# ALU.net
KiCad netlist of a schematic drawn in Altium Designer
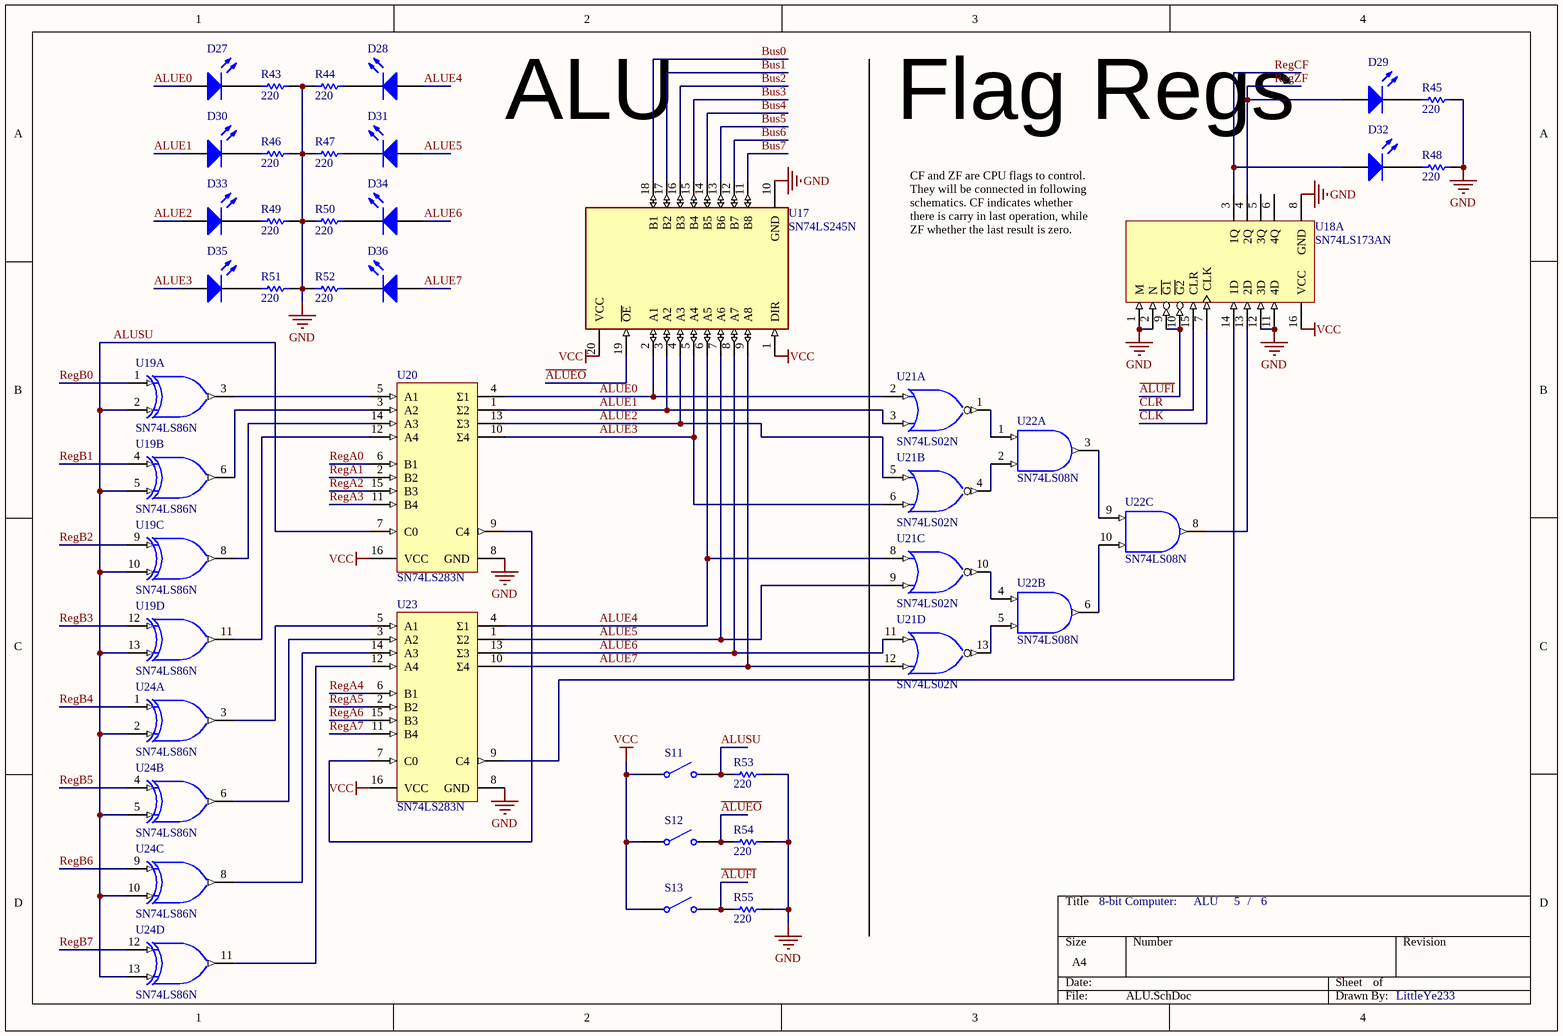
[diagram p0: ALU.SchDoc]

(export (version "E")
  (design (tool "Eeschema 10.0.6"))
  (components
    (comp (ref "D27")
      (value "Light-Emitting Diode")
      (libsource (lib "Simulation Generic Components") (part "LED"))
    )
    (comp (ref "D28")
      (value "Light-Emitting Diode")
      (libsource (lib "Simulation Generic Components") (part "LED"))
    )
    (comp (ref "D29")
      (value "Light-Emitting Diode")
      (libsource (lib "Simulation Generic Components") (part "LED"))
    )
    (comp (ref "D30")
      (value "Light-Emitting Diode")
      (libsource (lib "Simulation Generic Components") (part "LED"))
    )
    (comp (ref "D31")
      (value "Light-Emitting Diode")
      (libsource (lib "Simulation Generic Components") (part "LED"))
    )
    (comp (ref "D32")
      (value "Light-Emitting Diode")
      (libsource (lib "Simulation Generic Components") (part "LED"))
    )
    (comp (ref "D33")
      (value "Light-Emitting Diode")
      (libsource (lib "Simulation Generic Components") (part "LED"))
    )
    (comp (ref "D34")
      (value "Light-Emitting Diode")
      (libsource (lib "Simulation Generic Components") (part "LED"))
    )
    (comp (ref "D35")
      (value "Light-Emitting Diode")
      (libsource (lib "Simulation Generic Components") (part "LED"))
    )
    (comp (ref "D36")
      (value "Light-Emitting Diode")
      (libsource (lib "Simulation Generic Components") (part "LED"))
    )
    (comp (ref "R43")
      (value "220")
      (description "Resistor")
      (libsource (lib "Simulation Generic Components") (part "Resistor"))
    )
    (comp (ref "R44")
      (value "220")
      (description "Resistor")
      (libsource (lib "Simulation Generic Components") (part "Resistor"))
    )
    (comp (ref "R45")
      (value "220")
      (description "Resistor")
      (libsource (lib "Simulation Generic Components") (part "Resistor"))
    )
    (comp (ref "R46")
      (value "220")
      (description "Resistor")
      (libsource (lib "Simulation Generic Components") (part "Resistor"))
    )
    (comp (ref "R47")
      (value "220")
      (description "Resistor")
      (libsource (lib "Simulation Generic Components") (part "Resistor"))
    )
    (comp (ref "R48")
      (value "220")
      (description "Resistor")
      (libsource (lib "Simulation Generic Components") (part "Resistor"))
    )
    (comp (ref "R49")
      (value "220")
      (description "Resistor")
      (libsource (lib "Simulation Generic Components") (part "Resistor"))
    )
    (comp (ref "R50")
      (value "220")
      (description "Resistor")
      (libsource (lib "Simulation Generic Components") (part "Resistor"))
    )
    (comp (ref "R51")
      (value "220")
      (description "Resistor")
      (libsource (lib "Simulation Generic Components") (part "Resistor"))
    )
    (comp (ref "R52")
      (value "220")
      (description "Resistor")
      (libsource (lib "Simulation Generic Components") (part "Resistor"))
    )
    (comp (ref "R53")
      (value "220")
      (description "Resistor")
      (libsource (lib "Simulation Generic Components") (part "Resistor"))
    )
    (comp (ref "R54")
      (value "220")
      (description "Resistor")
      (libsource (lib "Simulation Generic Components") (part "Resistor"))
    )
    (comp (ref "R55")
      (value "220")
      (description "Resistor")
      (libsource (lib "Simulation Generic Components") (part "Resistor"))
    )
    (comp (ref "S11")
      (value "Single-Pole, Single-Throw Switch")
      (libsource (lib "Simulation Generic Components") (part "SPST SW"))
    )
    (comp (ref "S12")
      (value "Single-Pole, Single-Throw Switch")
      (libsource (lib "Simulation Generic Components") (part "SPST SW"))
    )
    (comp (ref "S13")
      (value "Single-Pole, Single-Throw Switch")
      (libsource (lib "Simulation Generic Components") (part "SPST SW"))
    )
    (comp (ref "U17")
      (value "SN74LS245N")
      (footprint "FP-N0020A-MFG")
      (description "IC TXRX NON-INVERT 5.25V 20DIP")
      (libsource (lib "SN74LS245N") (part "CMP-1620-00419-3"))
    )
    (comp (ref "U18")
      (value "SN74LS173AN")
      (footprint "N0016A")
      (description "4-Bit D-type Registers with 3-State Outputs, N0016A, TUBE")
      (fields
        (field (name "MANUFACTURER") "Texas Instruments")
        (field (name "GENERIC PART NUMBER") "SN74LS173A")
      )
      (libsource (lib "SN74LS173AN") (part "CMP-1619-00777-2"))
    )
    (comp (ref "U19") (value "SN74LS86N") (libsource (lib "SN74LS86N") (part "SN74LS86N")))
    (comp (ref "U20")
      (value "SN74LS283N")
      (footprint "N0016A")
      (description "4-Bit Binary Full Adders With Fast Carry, N0016A, TUBE")
      (fields
        (field (name "GENERIC PART NUMBER") "SN74LS283")
        (field (name "MANUFACTURER") "Texas Instruments")
      )
      (libsource (lib "SN74LS283N") (part "CMP-1623-00518-2"))
    )
    (comp (ref "U21")
      (value "SN74LS02N")
      (footprint "N0014A")
      (description "Quad 2-input positive-NOR gates, N0014A, TUBE")
      (fields
        (field (name "GENERIC PART NUMBER") "SN74LS02")
        (field (name "MANUFACTURER") "Texas Instruments")
      )
      (libsource (lib "SN74LS02N") (part "CMP-0806-00181-3"))
    )
    (comp (ref "U22")
      (value "SN74LS08N")
      (footprint "N0014A")
      (description "Quadruple 2-Input Positive-AND Gates, N0014A, TUBE")
      (fields
        (field (name "MANUFACTURER") "Texas Instruments")
        (field (name "GENERIC PART NUMBER") "SN74LS08")
      )
      (libsource (lib "SN74LS08N") (part "CMP-0777-00259-3"))
    )
    (comp (ref "U23")
      (value "SN74LS283N")
      (footprint "N0016A")
      (description "4-Bit Binary Full Adders With Fast Carry, N0016A, TUBE")
      (fields
        (field (name "GENERIC PART NUMBER") "SN74LS283")
        (field (name "MANUFACTURER") "Texas Instruments")
      )
      (libsource (lib "SN74LS283N") (part "CMP-1623-00518-2"))
    )
    (comp (ref "U24") (value "SN74LS86N") (libsource (lib "SN74LS86N") (part "SN74LS86N")))
  )
  (nets
    (net (code "1") (name "/ALUE0") (class "Default")
      (node (ref "D27") (pin "1") (pinfunction "A_1") (pintype "passive"))
      (node (ref "U17") (pin "2") (pinfunction "A1_2") (pintype "bidirectional"))
      (node (ref "U20") (pin "4") (pinfunction "Σ1_4") (pintype "passive"))
      (node (ref "U21") (pin "2") (pinfunction "1A_2") (pintype "input"))
    )
    (net (code "2") (name "/ALUE1") (class "Default")
      (node (ref "D30") (pin "1") (pinfunction "A_1") (pintype "passive"))
      (node (ref "U17") (pin "3") (pinfunction "A2_3") (pintype "bidirectional"))
      (node (ref "U20") (pin "1") (pinfunction "Σ2_1") (pintype "passive"))
      (node (ref "U21") (pin "3") (pinfunction "1B_3") (pintype "input"))
    )
    (net (code "3") (name "/ALUE2") (class "Default")
      (node (ref "D33") (pin "1") (pinfunction "A_1") (pintype "passive"))
      (node (ref "U17") (pin "4") (pinfunction "A3_4") (pintype "bidirectional"))
      (node (ref "U20") (pin "13") (pinfunction "Σ3_13") (pintype "passive"))
      (node (ref "U21") (pin "5") (pinfunction "2A_5") (pintype "input"))
    )
    (net (code "4") (name "/ALUE3") (class "Default")
      (node (ref "D35") (pin "1") (pinfunction "A_1") (pintype "passive"))
      (node (ref "U17") (pin "5") (pinfunction "A4_5") (pintype "bidirectional"))
      (node (ref "U20") (pin "10") (pinfunction "Σ4_10") (pintype "passive"))
      (node (ref "U21") (pin "6") (pinfunction "2B_6") (pintype "input"))
    )
    (net (code "5") (name "/ALUE4") (class "Default")
      (node (ref "D28") (pin "1") (pinfunction "A_1") (pintype "passive"))
      (node (ref "U17") (pin "6") (pinfunction "A5_6") (pintype "bidirectional"))
      (node (ref "U21") (pin "8") (pinfunction "3A_8") (pintype "input"))
      (node (ref "U23") (pin "4") (pinfunction "Σ1_4") (pintype "passive"))
    )
    (net (code "6") (name "/ALUE5") (class "Default")
      (node (ref "D31") (pin "1") (pinfunction "A_1") (pintype "passive"))
      (node (ref "U17") (pin "7") (pinfunction "A6_7") (pintype "bidirectional"))
      (node (ref "U21") (pin "9") (pinfunction "3B_9") (pintype "input"))
      (node (ref "U23") (pin "1") (pinfunction "Σ2_1") (pintype "passive"))
    )
    (net (code "7") (name "/ALUE6") (class "Default")
      (node (ref "D34") (pin "1") (pinfunction "A_1") (pintype "passive"))
      (node (ref "U17") (pin "8") (pinfunction "A7_8") (pintype "bidirectional"))
      (node (ref "U21") (pin "11") (pinfunction "4A_11") (pintype "input"))
      (node (ref "U23") (pin "13") (pinfunction "Σ3_13") (pintype "passive"))
    )
    (net (code "8") (name "/ALUE7") (class "Default")
      (node (ref "D36") (pin "1") (pinfunction "A_1") (pintype "passive"))
      (node (ref "U17") (pin "9") (pinfunction "A8_9") (pintype "bidirectional"))
      (node (ref "U21") (pin "12") (pinfunction "4B_12") (pintype "input"))
      (node (ref "U23") (pin "10") (pinfunction "Σ4_10") (pintype "passive"))
    )
    (net (code "9") (name "/ALUSU") (class "Default")
      (node (ref "R53") (pin "2") (pinfunction "2_2") (pintype "passive"))
      (node (ref "S11") (pin "2") (pinfunction "2_2") (pintype "passive"))
      (node (ref "U19") (pin "10") (pinfunction "3B_10") (pintype "input"))
      (node (ref "U19") (pin "13") (pinfunction "4B_13") (pintype "input"))
      (node (ref "U19") (pin "2") (pinfunction "1B_2") (pintype "input"))
      (node (ref "U19") (pin "5") (pinfunction "2B_5") (pintype "input"))
      (node (ref "U20") (pin "7") (pinfunction "C0_7") (pintype "input"))
      (node (ref "U24") (pin "10") (pinfunction "3B_10") (pintype "input"))
      (node (ref "U24") (pin "13") (pinfunction "4B_13") (pintype "input"))
      (node (ref "U24") (pin "2") (pinfunction "1B_2") (pintype "input"))
      (node (ref "U24") (pin "5") (pinfunction "2B_5") (pintype "input"))
    )
    (net (code "10") (name "/Bus0") (class "Default")
      (node (ref "U17") (pin "18") (pinfunction "B1_18") (pintype "bidirectional"))
    )
    (net (code "11") (name "/Bus1") (class "Default")
      (node (ref "U17") (pin "17") (pinfunction "B2_17") (pintype "bidirectional"))
    )
    (net (code "12") (name "/Bus2") (class "Default")
      (node (ref "U17") (pin "16") (pinfunction "B3_16") (pintype "bidirectional"))
    )
    (net (code "13") (name "/Bus3") (class "Default")
      (node (ref "U17") (pin "15") (pinfunction "B4_15") (pintype "bidirectional"))
    )
    (net (code "14") (name "/Bus4") (class "Default")
      (node (ref "U17") (pin "14") (pinfunction "B5_14") (pintype "bidirectional"))
    )
    (net (code "15") (name "/Bus5") (class "Default")
      (node (ref "U17") (pin "13") (pinfunction "B6_13") (pintype "bidirectional"))
    )
    (net (code "16") (name "/Bus6") (class "Default")
      (node (ref "U17") (pin "12") (pinfunction "B7_12") (pintype "bidirectional"))
    )
    (net (code "17") (name "/Bus7") (class "Default")
      (node (ref "U17") (pin "11") (pinfunction "B8_11") (pintype "bidirectional"))
    )
    (net (code "18") (name "/CLK") (class "Default")
      (node (ref "U18") (pin "7") (pinfunction "CLK_7") (pintype "input"))
    )
    (net (code "19") (name "/CLR") (class "Default")
      (node (ref "U18") (pin "15") (pinfunction "CLR_15") (pintype "input"))
    )
    (net (code "20") (name "/RegA0") (class "Default")
      (node (ref "U20") (pin "6") (pinfunction "B1_6") (pintype "input"))
    )
    (net (code "21") (name "/RegA1") (class "Default")
      (node (ref "U20") (pin "2") (pinfunction "B2_2") (pintype "input"))
    )
    (net (code "22") (name "/RegA2") (class "Default")
      (node (ref "U20") (pin "15") (pinfunction "B3_15") (pintype "input"))
    )
    (net (code "23") (name "/RegA3") (class "Default")
      (node (ref "U20") (pin "11") (pinfunction "B4_11") (pintype "input"))
    )
    (net (code "24") (name "/RegA4") (class "Default")
      (node (ref "U23") (pin "6") (pinfunction "B1_6") (pintype "input"))
    )
    (net (code "25") (name "/RegA5") (class "Default")
      (node (ref "U23") (pin "2") (pinfunction "B2_2") (pintype "input"))
    )
    (net (code "26") (name "/RegA6") (class "Default")
      (node (ref "U23") (pin "15") (pinfunction "B3_15") (pintype "input"))
    )
    (net (code "27") (name "/RegA7") (class "Default")
      (node (ref "U23") (pin "11") (pinfunction "B4_11") (pintype "input"))
    )
    (net (code "28") (name "/RegB0") (class "Default")
      (node (ref "U19") (pin "1") (pinfunction "1A_1") (pintype "input"))
    )
    (net (code "29") (name "/RegB1") (class "Default")
      (node (ref "U19") (pin "4") (pinfunction "2A_4") (pintype "input"))
    )
    (net (code "30") (name "/RegB2") (class "Default")
      (node (ref "U19") (pin "9") (pinfunction "3A_9") (pintype "input"))
    )
    (net (code "31") (name "/RegB3") (class "Default")
      (node (ref "U19") (pin "12") (pinfunction "4A_12") (pintype "input"))
    )
    (net (code "32") (name "/RegB4") (class "Default")
      (node (ref "U24") (pin "1") (pinfunction "1A_1") (pintype "input"))
    )
    (net (code "33") (name "/RegB5") (class "Default")
      (node (ref "U24") (pin "4") (pinfunction "2A_4") (pintype "input"))
    )
    (net (code "34") (name "/RegB6") (class "Default")
      (node (ref "U24") (pin "9") (pinfunction "3A_9") (pintype "input"))
    )
    (net (code "35") (name "/RegB7") (class "Default")
      (node (ref "U24") (pin "12") (pinfunction "4A_12") (pintype "input"))
    )
    (net (code "36") (name "/RegCF") (class "Default")
      (node (ref "D32") (pin "1") (pinfunction "A_1") (pintype "passive"))
      (node (ref "U18") (pin "3") (pinfunction "1Q_3") (pintype "tri_state"))
    )
    (net (code "37") (name "/RegZF") (class "Default")
      (node (ref "D29") (pin "1") (pinfunction "A_1") (pintype "passive"))
      (node (ref "U18") (pin "4") (pinfunction "2Q_4") (pintype "tri_state"))
    )
    (net (code "38") (name "/~{ALUEO}") (class "Default")
      (node (ref "R54") (pin "2") (pinfunction "2_2") (pintype "passive"))
      (node (ref "S12") (pin "2") (pinfunction "2_2") (pintype "passive"))
      (node (ref "U17") (pin "19") (pinfunction "~{OE}_19") (pintype "input"))
    )
    (net (code "39") (name "/~{ALUFI}") (class "Default")
      (node (ref "R55") (pin "2") (pinfunction "2_2") (pintype "passive"))
      (node (ref "S13") (pin "2") (pinfunction "2_2") (pintype "passive"))
      (node (ref "U18") (pin "10") (pinfunction "~{G2}_10") (pintype "input"))
      (node (ref "U18") (pin "9") (pinfunction "~{G1}_9") (pintype "input"))
    )
    (net (code "40") (name "GND") (class "Default")
      (node (ref "R43") (pin "2") (pinfunction "2_2") (pintype "passive"))
      (node (ref "R44") (pin "1") (pinfunction "1_1") (pintype "passive"))
      (node (ref "R45") (pin "2") (pinfunction "2_2") (pintype "passive"))
      (node (ref "R46") (pin "2") (pinfunction "2_2") (pintype "passive"))
      (node (ref "R47") (pin "1") (pinfunction "1_1") (pintype "passive"))
      (node (ref "R48") (pin "2") (pinfunction "2_2") (pintype "passive"))
      (node (ref "R49") (pin "2") (pinfunction "2_2") (pintype "passive"))
      (node (ref "R50") (pin "1") (pinfunction "1_1") (pintype "passive"))
      (node (ref "R51") (pin "2") (pinfunction "2_2") (pintype "passive"))
      (node (ref "R52") (pin "1") (pinfunction "1_1") (pintype "passive"))
      (node (ref "R53") (pin "1") (pinfunction "1_1") (pintype "passive"))
      (node (ref "R54") (pin "1") (pinfunction "1_1") (pintype "passive"))
      (node (ref "R55") (pin "1") (pinfunction "1_1") (pintype "passive"))
      (node (ref "U17") (pin "10") (pinfunction "GND_10") (pintype "power_in"))
      (node (ref "U18") (pin "1") (pinfunction "M_1") (pintype "input"))
      (node (ref "U18") (pin "11") (pinfunction "4D_11") (pintype "input"))
      (node (ref "U18") (pin "12") (pinfunction "3D_12") (pintype "input"))
      (node (ref "U18") (pin "2") (pinfunction "N_2") (pintype "input"))
      (node (ref "U18") (pin "8") (pinfunction "GND_8") (pintype "power_in"))
      (node (ref "U20") (pin "8") (pinfunction "GND_8") (pintype "power_in"))
      (node (ref "U23") (pin "8") (pinfunction "GND_8") (pintype "power_in"))
    )
    (net (code "41") (name "Net-(D27-K)") (class "Default")
      (node (ref "D27") (pin "2") (pinfunction "K_2") (pintype "passive"))
      (node (ref "R43") (pin "1") (pinfunction "1_1") (pintype "passive"))
    )
    (net (code "42") (name "Net-(D28-K)") (class "Default")
      (node (ref "D28") (pin "2") (pinfunction "K_2") (pintype "passive"))
      (node (ref "R44") (pin "2") (pinfunction "2_2") (pintype "passive"))
    )
    (net (code "43") (name "Net-(D29-K)") (class "Default")
      (node (ref "D29") (pin "2") (pinfunction "K_2") (pintype "passive"))
      (node (ref "R45") (pin "1") (pinfunction "1_1") (pintype "passive"))
    )
    (net (code "44") (name "Net-(D30-K)") (class "Default")
      (node (ref "D30") (pin "2") (pinfunction "K_2") (pintype "passive"))
      (node (ref "R46") (pin "1") (pinfunction "1_1") (pintype "passive"))
    )
    (net (code "45") (name "Net-(D31-K)") (class "Default")
      (node (ref "D31") (pin "2") (pinfunction "K_2") (pintype "passive"))
      (node (ref "R47") (pin "2") (pinfunction "2_2") (pintype "passive"))
    )
    (net (code "46") (name "Net-(D32-K)") (class "Default")
      (node (ref "D32") (pin "2") (pinfunction "K_2") (pintype "passive"))
      (node (ref "R48") (pin "1") (pinfunction "1_1") (pintype "passive"))
    )
    (net (code "47") (name "Net-(D33-K)") (class "Default")
      (node (ref "D33") (pin "2") (pinfunction "K_2") (pintype "passive"))
      (node (ref "R49") (pin "1") (pinfunction "1_1") (pintype "passive"))
    )
    (net (code "48") (name "Net-(D34-K)") (class "Default")
      (node (ref "D34") (pin "2") (pinfunction "K_2") (pintype "passive"))
      (node (ref "R50") (pin "2") (pinfunction "2_2") (pintype "passive"))
    )
    (net (code "49") (name "Net-(D35-K)") (class "Default")
      (node (ref "D35") (pin "2") (pinfunction "K_2") (pintype "passive"))
      (node (ref "R51") (pin "1") (pinfunction "1_1") (pintype "passive"))
    )
    (net (code "50") (name "Net-(D36-K)") (class "Default")
      (node (ref "D36") (pin "2") (pinfunction "K_2") (pintype "passive"))
      (node (ref "R52") (pin "2") (pinfunction "2_2") (pintype "passive"))
    )
    (net (code "51") (name "Net-(U18-1D)") (class "Default")
      (node (ref "U18") (pin "14") (pinfunction "1D_14") (pintype "input"))
      (node (ref "U23") (pin "9") (pinfunction "C4_9") (pintype "output"))
    )
    (net (code "52") (name "Net-(U18-2D)") (class "Default")
      (node (ref "U18") (pin "13") (pinfunction "2D_13") (pintype "input"))
      (node (ref "U22") (pin "8") (pinfunction "3Y_8") (pintype "output"))
    )
    (net (code "53") (name "Net-(U19A-1Y)") (class "Default")
      (node (ref "U19") (pin "3") (pinfunction "1Y_3") (pintype "output"))
      (node (ref "U20") (pin "5") (pinfunction "A1_5") (pintype "input"))
    )
    (net (code "54") (name "Net-(U19B-2Y)") (class "Default")
      (node (ref "U19") (pin "6") (pinfunction "2Y_6") (pintype "output"))
      (node (ref "U20") (pin "3") (pinfunction "A2_3") (pintype "input"))
    )
    (net (code "55") (name "Net-(U19C-3Y)") (class "Default")
      (node (ref "U19") (pin "8") (pinfunction "3Y_8") (pintype "output"))
      (node (ref "U20") (pin "14") (pinfunction "A3_14") (pintype "input"))
    )
    (net (code "56") (name "Net-(U19D-4Y)") (class "Default")
      (node (ref "U19") (pin "11") (pinfunction "4Y_11") (pintype "output"))
      (node (ref "U20") (pin "12") (pinfunction "A4_12") (pintype "input"))
    )
    (net (code "57") (name "Net-(U20-C4)") (class "Default")
      (node (ref "U20") (pin "9") (pinfunction "C4_9") (pintype "output"))
      (node (ref "U23") (pin "7") (pinfunction "C0_7") (pintype "input"))
    )
    (net (code "58") (name "Net-(U21A-1Y)") (class "Default")
      (node (ref "U21") (pin "1") (pinfunction "1Y_1") (pintype "output"))
      (node (ref "U22") (pin "1") (pinfunction "1A_1") (pintype "input"))
    )
    (net (code "59") (name "Net-(U21B-2Y)") (class "Default")
      (node (ref "U21") (pin "4") (pinfunction "2Y_4") (pintype "output"))
      (node (ref "U22") (pin "2") (pinfunction "1B_2") (pintype "input"))
    )
    (net (code "60") (name "Net-(U21C-3Y)") (class "Default")
      (node (ref "U21") (pin "10") (pinfunction "3Y_10") (pintype "output"))
      (node (ref "U22") (pin "4") (pinfunction "2A_4") (pintype "input"))
    )
    (net (code "61") (name "Net-(U21D-4Y)") (class "Default")
      (node (ref "U21") (pin "13") (pinfunction "4Y_13") (pintype "output"))
      (node (ref "U22") (pin "5") (pinfunction "2B_5") (pintype "input"))
    )
    (net (code "62") (name "Net-(U22A-1Y)") (class "Default")
      (node (ref "U22") (pin "3") (pinfunction "1Y_3") (pintype "output"))
      (node (ref "U22") (pin "9") (pinfunction "3A_9") (pintype "input"))
    )
    (net (code "63") (name "Net-(U22B-2Y)") (class "Default")
      (node (ref "U22") (pin "10") (pinfunction "3B_10") (pintype "input"))
      (node (ref "U22") (pin "6") (pinfunction "2Y_6") (pintype "output"))
    )
    (net (code "64") (name "Net-(U23-A1)") (class "Default")
      (node (ref "U23") (pin "5") (pinfunction "A1_5") (pintype "input"))
      (node (ref "U24") (pin "3") (pinfunction "1Y_3") (pintype "output"))
    )
    (net (code "65") (name "Net-(U23-A2)") (class "Default")
      (node (ref "U23") (pin "3") (pinfunction "A2_3") (pintype "input"))
      (node (ref "U24") (pin "6") (pinfunction "2Y_6") (pintype "output"))
    )
    (net (code "66") (name "Net-(U23-A3)") (class "Default")
      (node (ref "U23") (pin "14") (pinfunction "A3_14") (pintype "input"))
      (node (ref "U24") (pin "8") (pinfunction "3Y_8") (pintype "output"))
    )
    (net (code "67") (name "Net-(U23-A4)") (class "Default")
      (node (ref "U23") (pin "12") (pinfunction "A4_12") (pintype "input"))
      (node (ref "U24") (pin "11") (pinfunction "4Y_11") (pintype "output"))
    )
    (net (code "68") (name "VCC") (class "Default")
      (node (ref "S11") (pin "1") (pinfunction "1_1") (pintype "passive"))
      (node (ref "S12") (pin "1") (pinfunction "1_1") (pintype "passive"))
      (node (ref "S13") (pin "1") (pinfunction "1_1") (pintype "passive"))
      (node (ref "U17") (pin "1") (pinfunction "DIR_1") (pintype "input"))
      (node (ref "U17") (pin "20") (pinfunction "VCC_20") (pintype "power_in"))
      (node (ref "U18") (pin "16") (pinfunction "VCC_16") (pintype "power_in"))
      (node (ref "U20") (pin "16") (pinfunction "VCC_16") (pintype "power_in"))
      (node (ref "U23") (pin "16") (pinfunction "VCC_16") (pintype "power_in"))
    )
    (net (code "69") (name "unconnected-(U18-3Q-Pad5)") (class "Default")
      (node (ref "U18") (pin "5") (pinfunction "3Q_5") (pintype "tri_state"))
    )
    (net (code "70") (name "unconnected-(U18-4Q-Pad6)") (class "Default")
      (node (ref "U18") (pin "6") (pinfunction "4Q_6") (pintype "tri_state"))
    )
  )
)
